# ECU_Sheet1.net
KiCad netlist of a schematic drawn in Altium Designer
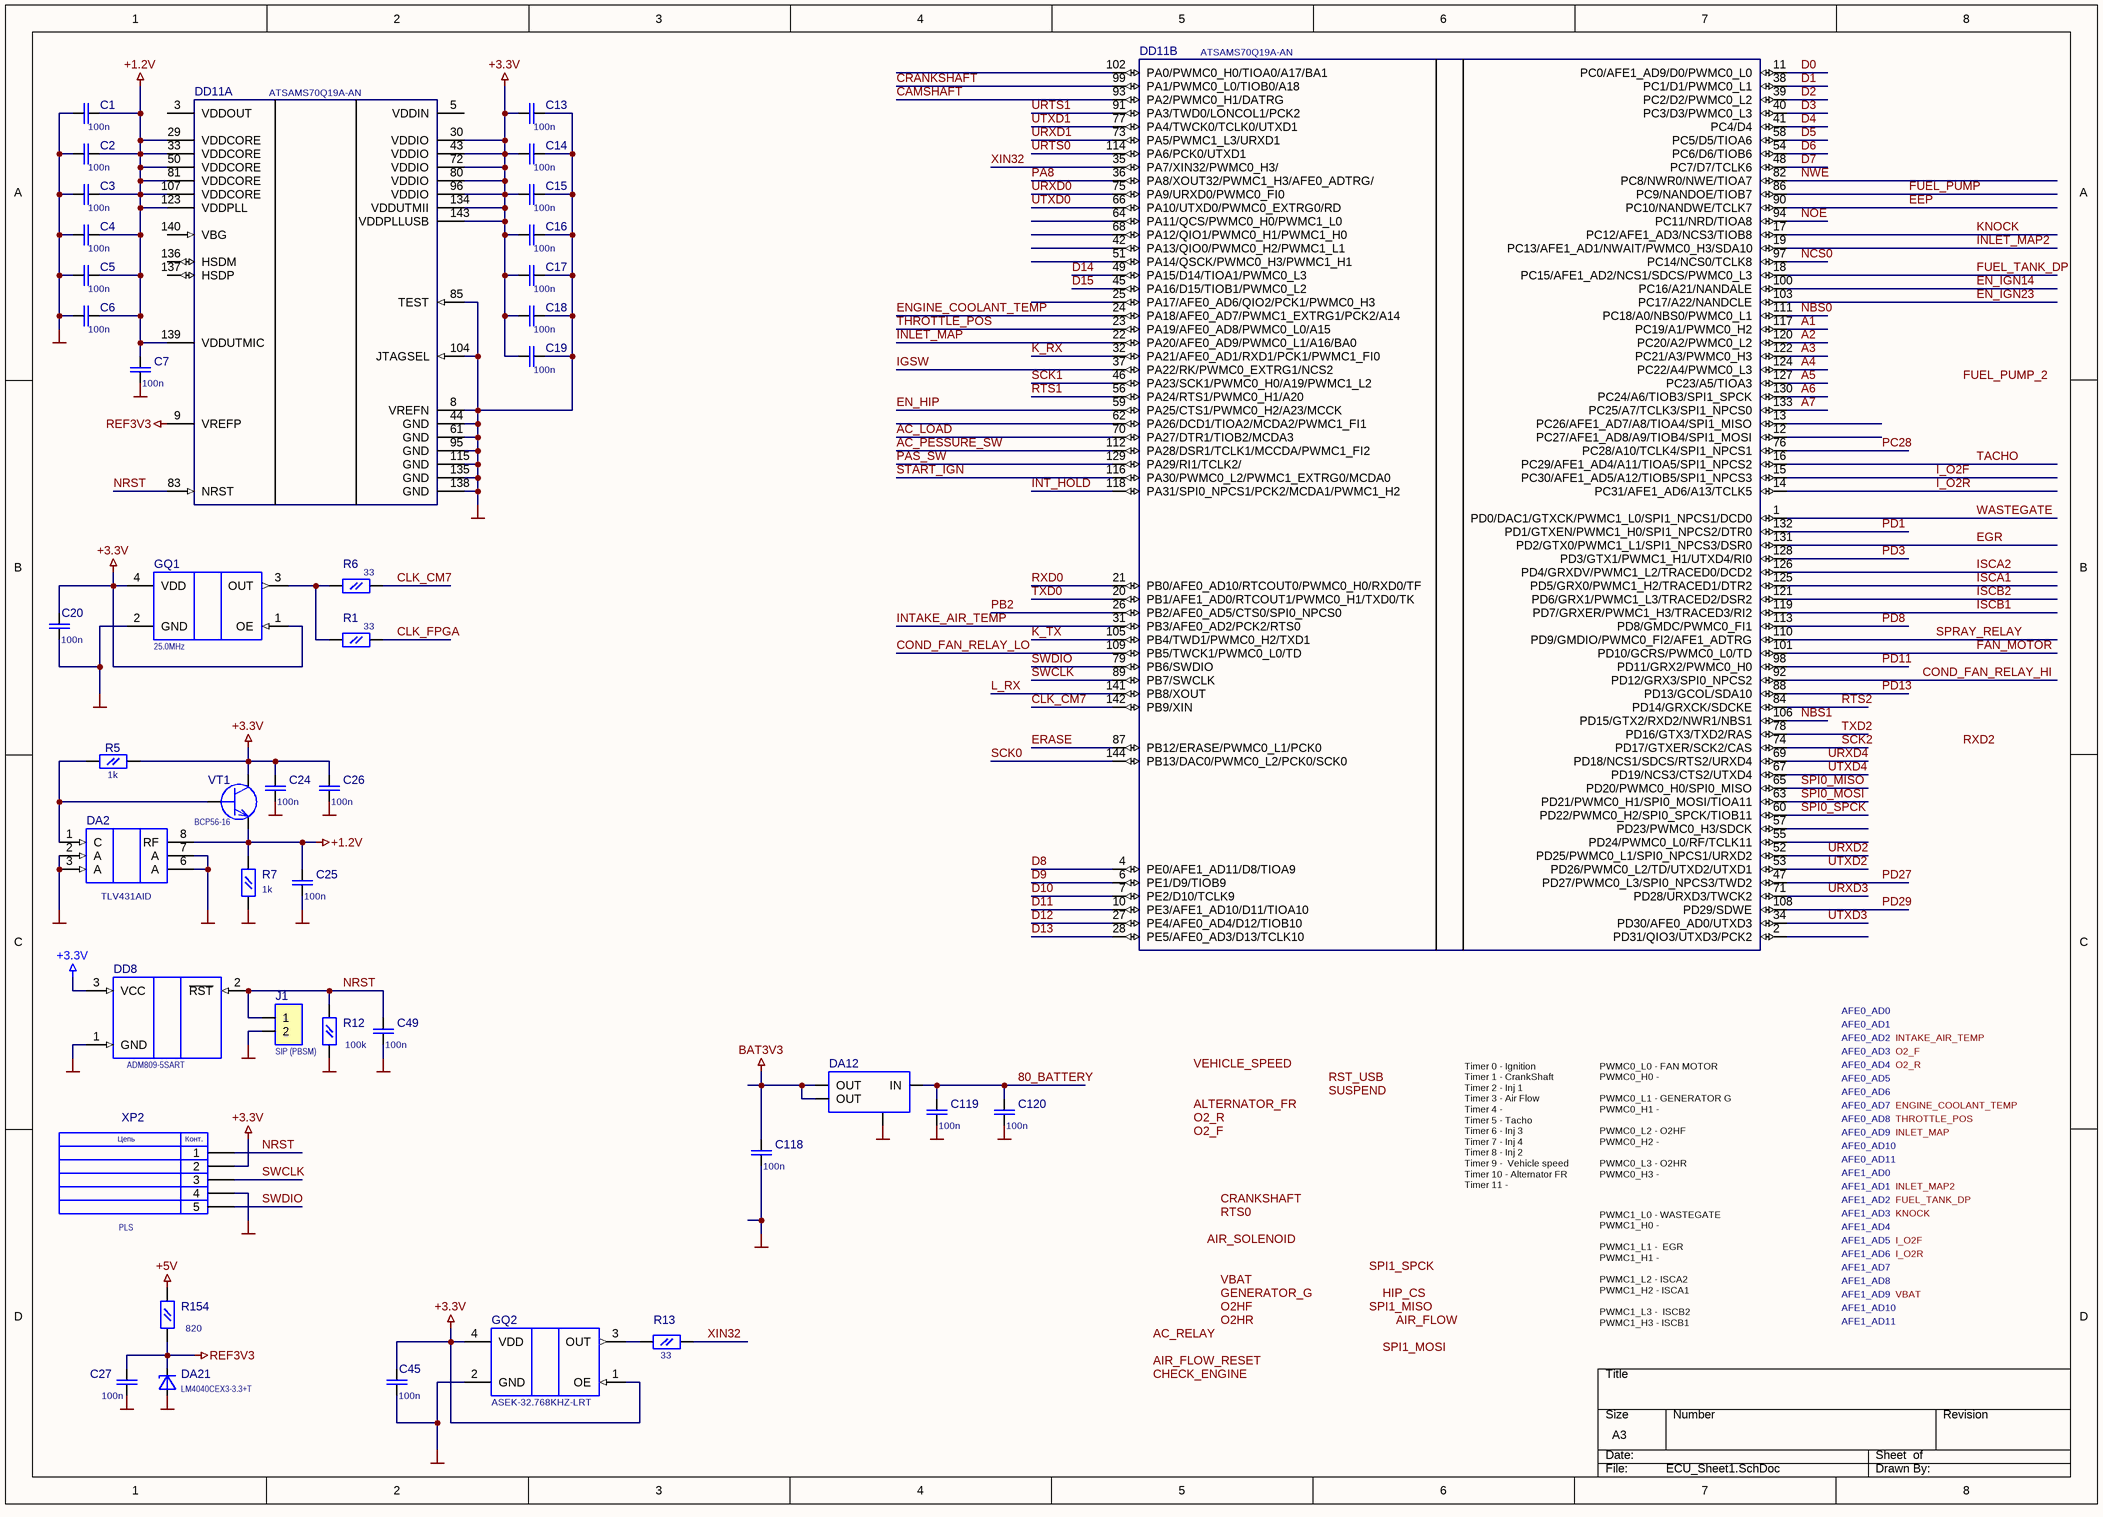
[diagram p0: ECU_Sheet1.SchDoc]

(export (version "E")
  (design (tool "Eeschema 10.0.6"))
  (components
    (comp (ref "C1")
      (value "100n")
      (footprint "C0603L")
      (description "C0603")
      (fields (field (name "Comment") "0.1мкФ-25В-X8R-10%"))
      (libsource (lib "L1") (part "CSMD"))
    )
    (comp (ref "C2")
      (value "100n")
      (footprint "C0603L")
      (description "C0603")
      (fields (field (name "Comment") "0.1мкФ-25В-X8R-10%"))
      (libsource (lib "L1") (part "CSMD"))
    )
    (comp (ref "C3")
      (value "100n")
      (footprint "C0603L")
      (description "C0603")
      (fields (field (name "Comment") "0.1мкФ-25В-X8R-10%"))
      (libsource (lib "L1") (part "CSMD"))
    )
    (comp (ref "C4")
      (value "100n")
      (footprint "C0603L")
      (description "C0603")
      (fields (field (name "Comment") "0.1мкФ-25В-X8R-10%"))
      (libsource (lib "L1") (part "CSMD"))
    )
    (comp (ref "C5")
      (value "100n")
      (footprint "C0603L")
      (description "C0603")
      (fields (field (name "Comment") "0.1мкФ-25В-X8R-10%"))
      (libsource (lib "L1") (part "CSMD"))
    )
    (comp (ref "C6")
      (value "100n")
      (footprint "C0603L")
      (description "C0603")
      (fields (field (name "Comment") "0.1мкФ-25В-X8R-10%"))
      (libsource (lib "L1") (part "CSMD"))
    )
    (comp (ref "C7")
      (value "100n")
      (footprint "C0603L")
      (description "C0603")
      (fields (field (name "Comment") "0.1мкФ-25В-X8R-10%"))
      (libsource (lib "L1") (part "CSMD"))
    )
    (comp (ref "C13")
      (value "100n")
      (footprint "C0603L")
      (description "C0603")
      (fields (field (name "Comment") "0.1мкФ-25В-X8R-10%"))
      (libsource (lib "L1") (part "CSMD"))
    )
    (comp (ref "C14")
      (value "100n")
      (footprint "C0603L")
      (description "C0603")
      (fields (field (name "Comment") "0.1мкФ-25В-X8R-10%"))
      (libsource (lib "L1") (part "CSMD"))
    )
    (comp (ref "C15")
      (value "100n")
      (footprint "C0603L")
      (description "C0603")
      (fields (field (name "Comment") "0.1мкФ-25В-X8R-10%"))
      (libsource (lib "L1") (part "CSMD"))
    )
    (comp (ref "C16")
      (value "100n")
      (footprint "C0603L")
      (description "C0603")
      (fields (field (name "Comment") "0.1мкФ-25В-X8R-10%"))
      (libsource (lib "L1") (part "CSMD"))
    )
    (comp (ref "C17")
      (value "100n")
      (footprint "C0603L")
      (description "C0603")
      (fields (field (name "Comment") "0.1мкФ-25В-X8R-10%"))
      (libsource (lib "L1") (part "CSMD"))
    )
    (comp (ref "C18")
      (value "100n")
      (footprint "C0603L")
      (description "C0603")
      (fields (field (name "Comment") "0.1мкФ-25В-X8R-10%"))
      (libsource (lib "L1") (part "CSMD"))
    )
    (comp (ref "C19")
      (value "100n")
      (footprint "C0603L")
      (description "C0603")
      (fields (field (name "Comment") "0.1мкФ-25В-X8R-10%"))
      (libsource (lib "L1") (part "CSMD"))
    )
    (comp (ref "C20")
      (value "100n")
      (footprint "C0805L")
      (description "C0603")
      (fields (field (name "Comment") "0.01мкФ-50В-X8R-10%"))
      (libsource (lib "L1") (part "CSMD"))
    )
    (comp (ref "C24")
      (value "100n")
      (footprint "C0805L")
      (description "C0603")
      (fields (field (name "Comment") "0.1мкФ-25В-X8R-10%"))
      (libsource (lib "L1") (part "CSMD"))
    )
    (comp (ref "C25")
      (value "100n")
      (footprint "C0805L")
      (description "C0603")
      (fields (field (name "Comment") "0.1мкФ-25В-X8R-10%"))
      (libsource (lib "L1") (part "CSMD"))
    )
    (comp (ref "C26")
      (value "100n")
      (footprint "C0805L")
      (description "C0603")
      (fields (field (name "Comment") "0.1мкФ-25В-X8R-10%"))
      (libsource (lib "L1") (part "CSMD"))
    )
    (comp (ref "C27")
      (value "100n")
      (footprint "C0603L")
      (description "C0603")
      (fields (field (name "Comment") "0.1мкФ-25В-X8R-10%"))
      (libsource (lib "L1") (part "CSMD"))
    )
    (comp (ref "C45")
      (value "100n")
      (footprint "C0805L")
      (description "C0603")
      (fields (field (name "Comment") "0.01мкФ-50В-X8R-10%"))
      (libsource (lib "L1") (part "CSMD"))
    )
    (comp (ref "C49")
      (value "100n")
      (footprint "C0603L")
      (description "C0603")
      (fields (field (name "Comment") "0.1мкФ-25В-X8R-10%"))
      (libsource (lib "L1") (part "CSMD"))
    )
    (comp (ref "C118")
      (value "100n")
      (footprint "C0805L")
      (description "C0603")
      (fields (field (name "Comment") "0.1мкФ-25В-X8R-10%"))
      (libsource (lib "L1") (part "CSMD"))
    )
    (comp (ref "C119")
      (value "100n")
      (footprint "C0805L")
      (description "C0603")
      (fields (field (name "Comment") "CSMD"))
      (libsource (lib "L1") (part "CSMD"))
    )
    (comp (ref "C120")
      (value "100n")
      (footprint "C0805L")
      (description "C0603")
      (fields (field (name "Comment") "CSMD"))
      (libsource (lib "L1") (part "CSMD"))
    )
    (comp (ref "DA2") (value "TLV431AID") (footprint "SOIC8 JEDEC") (libsource (lib "L1") (part "TL431AID")))
    (comp (ref "DA12")
      (value "LM1117IMP-3.3")
      (footprint "SOT-223")
      (libsource (lib "RL1") (part "LM1117IMP-3.3"))
    )
    (comp (ref "DA21")
      (value "LM4040CEX3-3.3+T")
      (footprint "RL1:SOT-23")
      (description "Improved Precision Micropower Shunt Voltage Reference")
      (libsource (lib "L1") (part "LM4040"))
    )
    (comp (ref "DD8")
      (value "ADM809-5SART")
      (footprint "RL1:SOT-23")
      (libsource (lib "L1") (part "ADM809-5SART"))
    )
    (comp (ref "DD11")
      (value "ATSAMS70Q19A-AN")
      (footprint "LQFP144")
      (libsource (lib "L1") (part "ATSAMS70Q19A-AN"))
    )
    (comp (ref "GQ1")
      (value "25.0MHz")
      (footprint "KXO-97")
      (description "KXO-V97T 25.0 MHz")
      (libsource (lib "L1") (part "KXO-V97T"))
    )
    (comp (ref "GQ2")
      (value "ASEK-32.768KHZ-LRT")
      (footprint "QUARTZ-3.2mm-2.5mm")
      (libsource (lib "RL1") (part "ASEMB-50.000MHZ-LY"))
    )
    (comp (ref "J1") (value "SIP (PBSM)") (footprint "SIP1X2S") (libsource (lib "SCH") (part "CON2")))
    (comp (ref "R1")
      (value "33")
      (footprint "R0603L")
      (description "R0805")
      (fields (field (name "Comment") "33-5%"))
      (libsource (lib "L1") (part "RSMD"))
    )
    (comp (ref "R5")
      (value "1k")
      (footprint "R0805")
      (description "R0805")
      (fields (field (name "Comment") "1к-5%"))
      (libsource (lib "L1") (part "RSMD"))
    )
    (comp (ref "R6")
      (value "33")
      (footprint "R0603L")
      (description "R0805")
      (fields (field (name "Comment") "33-5%"))
      (libsource (lib "L1") (part "RSMD"))
    )
    (comp (ref "R7")
      (value "1k")
      (footprint "R0805L")
      (description "R0805")
      (fields (field (name "Comment") "1к-5%"))
      (libsource (lib "L1") (part "RSMD"))
    )
    (comp (ref "R12")
      (value "100k")
      (footprint "R0805L")
      (description "R0805")
      (fields (field (name "Comment") "100к-5%"))
      (libsource (lib "L1") (part "RSMD"))
    )
    (comp (ref "R13")
      (value "33")
      (footprint "R0603L")
      (description "R0805")
      (fields (field (name "Comment") "33-5%"))
      (libsource (lib "L1") (part "RSMD"))
    )
    (comp (ref "R154")
      (value "820")
      (footprint "R0805L")
      (description "R0805")
      (fields (field (name "Comment") "100к-5%"))
      (libsource (lib "L1") (part "RSMD"))
    )
    (comp (ref "VT1") (value "BCP56-16") (footprint "SOT-223 PWR") (libsource (lib "L1") (part "BCP56-16")))
    (comp (ref "XP2")
      (value "PLS")
      (footprint "SIP5")
      (description "CONNSIP5")
      (libsource (lib "RL1") (part "CONNSIP5"))
    )
  )
  (nets
    (net (code "1") (name "+1.2V") (class "Default")
      (node (ref "C1") (pin "1") (pintype "passive"))
      (node (ref "C2") (pin "1") (pintype "passive"))
      (node (ref "C25") (pin "1") (pintype "passive"))
      (node (ref "C3") (pin "1") (pintype "passive"))
      (node (ref "C4") (pin "1") (pintype "passive"))
      (node (ref "C5") (pin "1") (pintype "passive"))
      (node (ref "C6") (pin "1") (pintype "passive"))
      (node (ref "C7") (pin "1") (pintype "passive"))
      (node (ref "DA2") (pin "8") (pinfunction "RF_8") (pintype "power_in"))
      (node (ref "DD11") (pin "107") (pinfunction "VDDCORE_107") (pintype "power_in"))
      (node (ref "DD11") (pin "123") (pinfunction "VDDPLL_123") (pintype "power_in"))
      (node (ref "DD11") (pin "139") (pinfunction "VDDUTMIC_139") (pintype "power_in"))
      (node (ref "DD11") (pin "29") (pinfunction "VDDCORE_29") (pintype "power_in"))
      (node (ref "DD11") (pin "33") (pinfunction "VDDCORE_33") (pintype "power_in"))
      (node (ref "DD11") (pin "50") (pinfunction "VDDCORE_50") (pintype "power_in"))
      (node (ref "DD11") (pin "81") (pinfunction "VDDCORE_81") (pintype "power_in"))
      (node (ref "R7") (pin "2") (pinfunction "Pin2_2") (pintype "passive"))
      (node (ref "VT1") (pin "3") (pinfunction "E_3") (pintype "passive"))
    )
    (net (code "2") (name "+3.3V") (class "Default")
      (node (ref "C13") (pin "2") (pintype "passive"))
      (node (ref "C14") (pin "2") (pintype "passive"))
      (node (ref "C15") (pin "2") (pintype "passive"))
      (node (ref "C16") (pin "2") (pintype "passive"))
      (node (ref "C17") (pin "2") (pintype "passive"))
      (node (ref "C18") (pin "2") (pintype "passive"))
      (node (ref "C19") (pin "2") (pintype "passive"))
      (node (ref "C20") (pin "2") (pintype "passive"))
      (node (ref "C24") (pin "1") (pintype "passive"))
      (node (ref "C26") (pin "1") (pintype "passive"))
      (node (ref "C45") (pin "2") (pintype "passive"))
      (node (ref "DD11") (pin "134") (pinfunction "VDDUTMII_134") (pintype "power_in"))
      (node (ref "DD11") (pin "143") (pinfunction "VDDPLLUSB_143") (pintype "power_in"))
      (node (ref "DD11") (pin "30") (pinfunction "VDDIO_30") (pintype "power_in"))
      (node (ref "DD11") (pin "43") (pinfunction "VDDIO_43") (pintype "power_in"))
      (node (ref "DD11") (pin "72") (pinfunction "VDDIO_72") (pintype "power_in"))
      (node (ref "DD11") (pin "80") (pinfunction "VDDIO_80") (pintype "power_in"))
      (node (ref "DD11") (pin "96") (pinfunction "VDDIO_96") (pintype "power_in"))
      (node (ref "DD8") (pin "3") (pinfunction "VCC_3") (pintype "input"))
      (node (ref "GQ1") (pin "1") (pinfunction "OE_1") (pintype "input"))
      (node (ref "GQ1") (pin "4") (pinfunction "VDD_4") (pintype "power_in"))
      (node (ref "GQ2") (pin "1") (pinfunction "OE_1") (pintype "input"))
      (node (ref "GQ2") (pin "4") (pinfunction "VDD_4") (pintype "power_in"))
      (node (ref "R5") (pin "1") (pinfunction "Pin1_1") (pintype "passive"))
      (node (ref "VT1") (pin "2") (pinfunction "C_2") (pintype "passive"))
      (node (ref "XP2") (pin "2") (pinfunction "2_2") (pintype "passive"))
    )
    (net (code "3") (name "+5V") (class "Default")
      (node (ref "R154") (pin "2") (pinfunction "Pin2_2") (pintype "passive"))
    )
    (net (code "4") (name "/80_BATTERY") (class "Default")
      (node (ref "C119") (pin "1") (pintype "passive"))
      (node (ref "C120") (pin "1") (pintype "passive"))
      (node (ref "DA12") (pin "3") (pinfunction "IN_3") (pintype "passive"))
    )
    (net (code "5") (name "/A1") (class "Default")
      (node (ref "DD11") (pin "117") (pinfunction "PC19/A1/PWMC0_H2_117") (pintype "bidirectional"))
    )
    (net (code "6") (name "/A2") (class "Default")
      (node (ref "DD11") (pin "120") (pinfunction "PC20/A2/PWMC0_L2_120") (pintype "bidirectional"))
    )
    (net (code "7") (name "/A3") (class "Default")
      (node (ref "DD11") (pin "122") (pinfunction "PC21/A3/PWMC0_H3_122") (pintype "bidirectional"))
    )
    (net (code "8") (name "/A4") (class "Default")
      (node (ref "DD11") (pin "124") (pinfunction "PC22/A4/PWMC0_L3_124") (pintype "bidirectional"))
    )
    (net (code "9") (name "/A5") (class "Default")
      (node (ref "DD11") (pin "127") (pinfunction "PC23/A5/TIOA3_127") (pintype "bidirectional"))
    )
    (net (code "10") (name "/A6") (class "Default")
      (node (ref "DD11") (pin "130") (pinfunction "PC24/A6/TIOB3/SPI1_SPCK_130") (pintype "bidirectional"))
    )
    (net (code "11") (name "/A7") (class "Default")
      (node (ref "DD11") (pin "133") (pinfunction "PC25/A7/TCLK3/SPI1_NPCS0_133") (pintype "bidirectional"))
    )
    (net (code "12") (name "/AC_LOAD") (class "Default")
      (node (ref "DD11") (pin "70") (pinfunction "PA27/DTR1/TIOB2/MCDA3_70") (pintype "bidirectional"))
    )
    (net (code "13") (name "/AC_PESSURE_SW") (class "Default")
      (node (ref "DD11") (pin "112") (pinfunction "PA28/DSR1/TCLK1/MCCDA/PWMC1_FI2_112") (pintype "bidirectional"))
    )
    (net (code "19") (name "/CAMSHAFT") (class "Default")
      (node (ref "DD11") (pin "93") (pinfunction "PA2/PWMC0_H1/DATRG_93") (pintype "bidirectional"))
    )
    (net (code "21") (name "/CLK_CM7") (class "Default")
      (node (ref "DD11") (pin "142") (pinfunction "PB9/XIN_142") (pintype "bidirectional"))
      (node (ref "R6") (pin "2") (pinfunction "Pin2_2") (pintype "passive"))
    )
    (net (code "22") (name "/CLK_FPGA") (class "Default")
      (node (ref "R1") (pin "2") (pinfunction "Pin2_2") (pintype "passive"))
    )
    (net (code "23") (name "/COND_FAN_RELAY_HI") (class "Default")
      (node (ref "DD11") (pin "92") (pinfunction "PD12/GRX3/SPI0_NPCS2_92") (pintype "bidirectional"))
    )
    (net (code "24") (name "/COND_FAN_RELAY_LO") (class "Default")
      (node (ref "DD11") (pin "109") (pinfunction "PB5/TWCK1/PWMC0_L0/TD_109") (pintype "bidirectional"))
    )
    (net (code "25") (name "/CRANKSHAFT") (class "Default")
      (node (ref "DD11") (pin "99") (pinfunction "PA1/PWMC0_L0/TIOB0/A18_99") (pintype "bidirectional"))
    )
    (net (code "26") (name "/D0") (class "Default")
      (node (ref "DD11") (pin "11") (pinfunction "PC0/AFE1_AD9/D0/PWMC0_L0_11") (pintype "bidirectional"))
    )
    (net (code "27") (name "/D1") (class "Default")
      (node (ref "DD11") (pin "38") (pinfunction "PC1/D1/PWMC0_L1_38") (pintype "bidirectional"))
    )
    (net (code "28") (name "/D2") (class "Default")
      (node (ref "DD11") (pin "39") (pinfunction "PC2/D2/PWMC0_L2_39") (pintype "bidirectional"))
    )
    (net (code "29") (name "/D3") (class "Default")
      (node (ref "DD11") (pin "40") (pinfunction "PC3/D3/PWMC0_L3_40") (pintype "bidirectional"))
    )
    (net (code "30") (name "/D4") (class "Default")
      (node (ref "DD11") (pin "41") (pinfunction "PC4/D4_41") (pintype "bidirectional"))
    )
    (net (code "31") (name "/D5") (class "Default")
      (node (ref "DD11") (pin "58") (pinfunction "PC5/D5/TIOA6_58") (pintype "bidirectional"))
    )
    (net (code "32") (name "/D6") (class "Default")
      (node (ref "DD11") (pin "54") (pinfunction "PC6/D6/TIOB6_54") (pintype "bidirectional"))
    )
    (net (code "33") (name "/D7") (class "Default")
      (node (ref "DD11") (pin "48") (pinfunction "PC7/D7/TCLK6_48") (pintype "bidirectional"))
    )
    (net (code "34") (name "/D8") (class "Default")
      (node (ref "DD11") (pin "4") (pinfunction "PE0/AFE1_AD11/D8/TIOA9_4") (pintype "bidirectional"))
    )
    (net (code "35") (name "/D9") (class "Default")
      (node (ref "DD11") (pin "6") (pinfunction "PE1/D9/TIOB9_6") (pintype "bidirectional"))
    )
    (net (code "36") (name "/D10") (class "Default")
      (node (ref "DD11") (pin "7") (pinfunction "PE2/D10/TCLK9_7") (pintype "bidirectional"))
    )
    (net (code "37") (name "/D11") (class "Default")
      (node (ref "DD11") (pin "10") (pinfunction "PE3/AFE1_AD10/D11/TIOA10_10") (pintype "bidirectional"))
    )
    (net (code "38") (name "/D12") (class "Default")
      (node (ref "DD11") (pin "27") (pinfunction "PE4/AFE0_AD4/D12/TIOB10_27") (pintype "bidirectional"))
    )
    (net (code "39") (name "/D13") (class "Default")
      (node (ref "DD11") (pin "28") (pinfunction "PE5/AFE0_AD3/D13/TCLK10_28") (pintype "bidirectional"))
    )
    (net (code "40") (name "/D14") (class "Default")
      (node (ref "DD11") (pin "49") (pinfunction "PA15/D14/TIOA1/PWMC0_L3_49") (pintype "bidirectional"))
    )
    (net (code "41") (name "/D15") (class "Default")
      (node (ref "DD11") (pin "45") (pinfunction "PA16/D15/TIOB1/PWMC0_L2_45") (pintype "bidirectional"))
    )
    (net (code "42") (name "/EEP") (class "Default")
      (node (ref "DD11") (pin "90") (pinfunction "PC10/NANDWE/TCLK7_90") (pintype "bidirectional"))
    )
    (net (code "43") (name "/EGR") (class "Default")
      (node (ref "DD11") (pin "131") (pinfunction "PD2/GTX0/PWMC1_L1/SPI1_NPCS3/DSR0_131") (pintype "bidirectional"))
    )
    (net (code "44") (name "/ENGINE_COOLANT_TEMP") (class "Default")
      (node (ref "DD11") (pin "24") (pinfunction "PA18/AFE0_AD7/PWMC1_EXTRG1/PCK2/A14_24") (pintype "bidirectional"))
    )
    (net (code "45") (name "/EN_HIP") (class "Default")
      (node (ref "DD11") (pin "59") (pinfunction "PA25/CTS1/PWMC0_H2/A23/MCCK_59") (pintype "bidirectional"))
    )
    (net (code "46") (name "/EN_IGN14") (class "Default")
      (node (ref "DD11") (pin "100") (pinfunction "PC16/A21/NANDALE_100") (pintype "bidirectional"))
    )
    (net (code "47") (name "/EN_IGN23") (class "Default")
      (node (ref "DD11") (pin "103") (pinfunction "PC17/A22/NANDCLE_103") (pintype "bidirectional"))
    )
    (net (code "48") (name "/ERASE") (class "Default")
      (node (ref "DD11") (pin "87") (pinfunction "PB12/ERASE/PWMC0_L1/PCK0_87") (pintype "bidirectional"))
    )
    (net (code "49") (name "/FAN_MOTOR") (class "Default")
      (node (ref "DD11") (pin "101") (pinfunction "PD10/GCRS/PWMC0_L0/TD_101") (pintype "bidirectional"))
    )
    (net (code "50") (name "/FUEL_PUMP") (class "Default")
      (node (ref "DD11") (pin "86") (pinfunction "PC9/NANDOE/TIOB7_86") (pintype "bidirectional"))
    )
    (net (code "52") (name "/FUEL_TANK_DP") (class "Default")
      (node (ref "DD11") (pin "18") (pinfunction "PC15/AFE1_AD2/NCS1/SDCS/PWMC0_L3_18") (pintype "bidirectional"))
    )
    (net (code "55") (name "/IGSW") (class "Default")
      (node (ref "DD11") (pin "37") (pinfunction "PA22/RK/PWMC0_EXTRG1/NCS2_37") (pintype "bidirectional"))
    )
    (net (code "56") (name "/INLET_MAP") (class "Default")
      (node (ref "DD11") (pin "22") (pinfunction "PA20/AFE0_AD9/PWMC0_L1/A16/BA0_22") (pintype "bidirectional"))
    )
    (net (code "57") (name "/INLET_MAP2") (class "Default")
      (node (ref "DD11") (pin "19") (pinfunction "PC13/AFE1_AD1/NWAIT/PWMC0_H3/SDA10_19") (pintype "bidirectional"))
    )
    (net (code "58") (name "/INTAKE_AIR_TEMP") (class "Default")
      (node (ref "DD11") (pin "31") (pinfunction "PB3/AFE0_AD2/PCK2/RTS0_31") (pintype "bidirectional"))
    )
    (net (code "59") (name "/INT_HOLD") (class "Default")
      (node (ref "DD11") (pin "118") (pinfunction "PA31/SPI0_NPCS1/PCK2/MCDA1/PWMC1_H2_118") (pintype "bidirectional"))
    )
    (net (code "60") (name "/ISCA1") (class "Default")
      (node (ref "DD11") (pin "125") (pinfunction "PD5/GRX0/PWMC1_H2/TRACED1/DTR2_125") (pintype "bidirectional"))
    )
    (net (code "61") (name "/ISCA2") (class "Default")
      (node (ref "DD11") (pin "126") (pinfunction "PD4/GRXDV/PWMC1_L2/TRACED0/DCD2_126") (pintype "bidirectional"))
    )
    (net (code "62") (name "/ISCB1") (class "Default")
      (node (ref "DD11") (pin "119") (pinfunction "PD7/GRXER/PWMC1_H3/TRACED3/RI2_119") (pintype "bidirectional"))
    )
    (net (code "63") (name "/ISCB2") (class "Default")
      (node (ref "DD11") (pin "121") (pinfunction "PD6/GRX1/PWMC1_L3/TRACED2/DSR2_121") (pintype "bidirectional"))
    )
    (net (code "64") (name "/I_O2F") (class "Default")
      (node (ref "DD11") (pin "15") (pinfunction "PC30/AFE1_AD5/A12/TIOB5/SPI1_NPCS3_15") (pintype "bidirectional"))
    )
    (net (code "65") (name "/I_O2R") (class "Default")
      (node (ref "DD11") (pin "14") (pinfunction "PC31/AFE1_AD6/A13/TCLK5_14") (pintype "bidirectional"))
    )
    (net (code "66") (name "/KNOCK") (class "Default")
      (node (ref "DD11") (pin "17") (pinfunction "PC12/AFE1_AD3/NCS3/TIOB8_17") (pintype "bidirectional"))
    )
    (net (code "67") (name "/K_RX") (class "Default")
      (node (ref "DD11") (pin "32") (pinfunction "PA21/AFE0_AD1/RXD1/PCK1/PWMC1_FI0_32") (pintype "bidirectional"))
    )
    (net (code "68") (name "/K_TX") (class "Default")
      (node (ref "DD11") (pin "105") (pinfunction "PB4/TWD1/PWMC0_H2/TXD1_105") (pintype "bidirectional"))
    )
    (net (code "69") (name "/L_RX") (class "Default")
      (node (ref "DD11") (pin "141") (pinfunction "PB8/XOUT_141") (pintype "bidirectional"))
    )
    (net (code "70") (name "/NBS0") (class "Default")
      (node (ref "DD11") (pin "111") (pinfunction "PC18/A0/NBS0/PWMC0_L1_111") (pintype "bidirectional"))
    )
    (net (code "71") (name "/NBS1") (class "Default")
      (node (ref "DD11") (pin "106") (pinfunction "PD15/GTX2/RXD2/NWR1/NBS1_106") (pintype "bidirectional"))
    )
    (net (code "72") (name "/NCS0") (class "Default")
      (node (ref "DD11") (pin "97") (pinfunction "PC14/NCS0/TCLK8_97") (pintype "bidirectional"))
    )
    (net (code "73") (name "/NOE") (class "Default")
      (node (ref "DD11") (pin "94") (pinfunction "PC11/NRD/TIOA8_94") (pintype "bidirectional"))
    )
    (net (code "74") (name "/NRST") (class "Default")
      (node (ref "C49") (pin "1") (pintype "passive"))
      (node (ref "DD11") (pin "83") (pinfunction "NRST_83") (pintype "input"))
      (node (ref "DD8") (pin "2") (pinfunction "~{RST}_2") (pintype "input"))
      (node (ref "J1") (pin "1") (pinfunction "1_1") (pintype "passive"))
      (node (ref "R12") (pin "2") (pinfunction "Pin2_2") (pintype "passive"))
      (node (ref "XP2") (pin "1") (pinfunction "1_1") (pintype "passive"))
    )
    (net (code "75") (name "/NWE") (class "Default")
      (node (ref "DD11") (pin "82") (pinfunction "PC8/NWR0/NWE/TIOA7_82") (pintype "bidirectional"))
    )
    (net (code "80") (name "/PA8") (class "Default")
      (node (ref "DD11") (pin "36") (pinfunction "PA8/XOUT32/PWMC1_H3/AFE0_ADTRG/_36") (pintype "bidirectional"))
    )
    (net (code "81") (name "/PAS_SW") (class "Default")
      (node (ref "DD11") (pin "129") (pinfunction "PA29/RI1/TCLK2/_129") (pintype "bidirectional"))
    )
    (net (code "82") (name "/PB2") (class "Default")
      (node (ref "DD11") (pin "26") (pinfunction "PB2/AFE0_AD5/CTS0/SPI0_NPCS0_26") (pintype "bidirectional"))
    )
    (net (code "83") (name "/PC28") (class "Default")
      (node (ref "DD11") (pin "76") (pinfunction "PC28/A10/TCLK4/SPI1_NPCS1_76") (pintype "bidirectional"))
    )
    (net (code "84") (name "/PD1") (class "Default")
      (node (ref "DD11") (pin "132") (pinfunction "PD1/GTXEN/PWMC1_H0/SPI1_NPCS2/DTR0_132") (pintype "bidirectional"))
    )
    (net (code "85") (name "/PD3") (class "Default")
      (node (ref "DD11") (pin "128") (pinfunction "PD3/GTX1/PWMC1_H1/UTXD4/RI0_128") (pintype "bidirectional"))
    )
    (net (code "86") (name "/PD8") (class "Default")
      (node (ref "DD11") (pin "113") (pinfunction "PD8/GMDC/PWMC0_FI1_113") (pintype "bidirectional"))
    )
    (net (code "87") (name "/PD11") (class "Default")
      (node (ref "DD11") (pin "98") (pinfunction "PD11/GRX2/PWMC0_H0_98") (pintype "bidirectional"))
    )
    (net (code "88") (name "/PD13") (class "Default")
      (node (ref "DD11") (pin "88") (pinfunction "PD13/GCOL/SDA10_88") (pintype "bidirectional"))
    )
    (net (code "89") (name "/PD27") (class "Default")
      (node (ref "DD11") (pin "47") (pinfunction "PD27/PWMC0_L3/SPI0_NPCS3/TWD2_47") (pintype "bidirectional"))
    )
    (net (code "90") (name "/PD29") (class "Default")
      (node (ref "DD11") (pin "108") (pinfunction "PD29/SDWE_108") (pintype "bidirectional"))
    )
    (net (code "93") (name "/RTS1") (class "Default")
      (node (ref "DD11") (pin "56") (pinfunction "PA24/RTS1/PWMC0_H1/A20_56") (pintype "bidirectional"))
    )
    (net (code "94") (name "/RTS2") (class "Default")
      (node (ref "DD11") (pin "84") (pinfunction "PD14/GRXCK/SDCKE_84") (pintype "bidirectional"))
    )
    (net (code "95") (name "/RXD0") (class "Default")
      (node (ref "DD11") (pin "21") (pinfunction "PB0/AFE0_AD10/RTCOUT0/PWMC0_H0/RXD0/TF_21") (pintype "bidirectional"))
    )
    (net (code "97") (name "/SCK0") (class "Default")
      (node (ref "DD11") (pin "144") (pinfunction "PB13/DAC0/PWMC0_L2/PCK0/SCK0_144") (pintype "bidirectional"))
    )
    (net (code "98") (name "/SCK1") (class "Default")
      (node (ref "DD11") (pin "46") (pinfunction "PA23/SCK1/PWMC0_H0/A19/PWMC1_L2_46") (pintype "bidirectional"))
    )
    (net (code "99") (name "/SCK2") (class "Default")
      (node (ref "DD11") (pin "74") (pinfunction "PD17/GTXER/SCK2/CAS_74") (pintype "bidirectional"))
    )
    (net (code "100") (name "/SPI0_MISO") (class "Default")
      (node (ref "DD11") (pin "65") (pinfunction "PD20/PWMC0_H0/SPI0_MISO_65") (pintype "bidirectional"))
    )
    (net (code "101") (name "/SPI0_MOSI") (class "Default")
      (node (ref "DD11") (pin "63") (pinfunction "PD21/PWMC0_H1/SPI0_MOSI/TIOA11_63") (pintype "bidirectional"))
    )
    (net (code "102") (name "/SPI0_SPCK") (class "Default")
      (node (ref "DD11") (pin "60") (pinfunction "PD22/PWMC0_H2/SPI0_SPCK/TIOB11_60") (pintype "bidirectional"))
    )
    (net (code "106") (name "/SPRAY_RELAY") (class "Default")
      (node (ref "DD11") (pin "110") (pinfunction "PD9/GMDIO/PWMC0_FI2/AFE1_ADTRG_110") (pintype "bidirectional"))
    )
    (net (code "107") (name "/START_IGN") (class "Default")
      (node (ref "DD11") (pin "116") (pinfunction "PA30/PWMC0_L2/PWMC1_EXTRG0/MCDA0_116") (pintype "bidirectional"))
    )
    (net (code "109") (name "/SWCLK") (class "Default")
      (node (ref "DD11") (pin "89") (pinfunction "PB7/SWCLK_89") (pintype "bidirectional"))
      (node (ref "XP2") (pin "3") (pinfunction "3_3") (pintype "passive"))
    )
    (net (code "110") (name "/SWDIO") (class "Default")
      (node (ref "DD11") (pin "79") (pinfunction "PB6/SWDIO_79") (pintype "bidirectional"))
      (node (ref "XP2") (pin "5") (pinfunction "5_5") (pintype "passive"))
    )
    (net (code "111") (name "/TACHO") (class "Default")
      (node (ref "DD11") (pin "16") (pinfunction "PC29/AFE1_AD4/A11/TIOA5/SPI1_NPCS2_16") (pintype "bidirectional"))
    )
    (net (code "112") (name "/THROTTLE_POS") (class "Default")
      (node (ref "DD11") (pin "23") (pinfunction "PA19/AFE0_AD8/PWMC0_L0/A15_23") (pintype "bidirectional"))
    )
    (net (code "113") (name "/TXD0") (class "Default")
      (node (ref "DD11") (pin "20") (pinfunction "PB1/AFE1_AD0/RTCOUT1/PWMC0_H1/TXD0/TK_20") (pintype "bidirectional"))
    )
    (net (code "114") (name "/TXD2") (class "Default")
      (node (ref "DD11") (pin "78") (pinfunction "PD16/GTX3/TXD2/RAS_78") (pintype "bidirectional"))
    )
    (net (code "115") (name "/URTS0") (class "Default")
      (node (ref "DD11") (pin "114") (pinfunction "PA6/PCK0/UTXD1_114") (pintype "bidirectional"))
    )
    (net (code "116") (name "/URTS1") (class "Default")
      (node (ref "DD11") (pin "91") (pinfunction "PA3/TWD0/LONCOL1/PCK2_91") (pintype "bidirectional"))
    )
    (net (code "117") (name "/URXD0") (class "Default")
      (node (ref "DD11") (pin "75") (pinfunction "PA9/URXD0/PWMC0_FI0_75") (pintype "bidirectional"))
    )
    (net (code "118") (name "/URXD1") (class "Default")
      (node (ref "DD11") (pin "73") (pinfunction "PA5/PWMC1_L3/URXD1_73") (pintype "bidirectional"))
    )
    (net (code "119") (name "/URXD2") (class "Default")
      (node (ref "DD11") (pin "52") (pinfunction "PD25/PWMC0_L1/SPI0_NPCS1/URXD2_52") (pintype "bidirectional"))
    )
    (net (code "120") (name "/URXD3") (class "Default")
      (node (ref "DD11") (pin "71") (pinfunction "PD28/URXD3/TWCK2_71") (pintype "bidirectional"))
    )
    (net (code "121") (name "/URXD4") (class "Default")
      (node (ref "DD11") (pin "69") (pinfunction "PD18/NCS1/SDCS/RTS2/URXD4_69") (pintype "bidirectional"))
    )
    (net (code "122") (name "/UTXD0") (class "Default")
      (node (ref "DD11") (pin "66") (pinfunction "PA10/UTXD0/PWMC0_EXTRG0/RD_66") (pintype "bidirectional"))
    )
    (net (code "123") (name "/UTXD1") (class "Default")
      (node (ref "DD11") (pin "77") (pinfunction "PA4/TWCK0/TCLK0/UTXD1_77") (pintype "bidirectional"))
    )
    (net (code "124") (name "/UTXD2") (class "Default")
      (node (ref "DD11") (pin "53") (pinfunction "PD26/PWMC0_L2/TD/UTXD2/UTXD1_53") (pintype "bidirectional"))
    )
    (net (code "125") (name "/UTXD3") (class "Default")
      (node (ref "DD11") (pin "34") (pinfunction "PD30/AFE0_AD0/UTXD3_34") (pintype "bidirectional"))
    )
    (net (code "126") (name "/UTXD4") (class "Default")
      (node (ref "DD11") (pin "67") (pinfunction "PD19/NCS3/CTS2/UTXD4_67") (pintype "bidirectional"))
    )
    (net (code "129") (name "/WASTEGATE") (class "Default")
      (node (ref "DD11") (pin "1") (pinfunction "PD0/DAC1/GTXCK/PWMC1_L0/SPI1_NPCS1/DCD0_1") (pintype "bidirectional"))
    )
    (net (code "130") (name "/XIN32") (class "Default")
      (node (ref "DD11") (pin "35") (pinfunction "PA7/XIN32/PWMC0_H3/_35") (pintype "bidirectional"))
      (node (ref "R13") (pin "2") (pinfunction "Pin2_2") (pintype "passive"))
    )
    (net (code "131") (name "BAT3V3") (class "Default")
      (node (ref "C118") (pin "1") (pintype "passive"))
      (node (ref "DA12") (pin "2") (pinfunction "OUT_2") (pintype "passive"))
      (node (ref "DA12") (pin "4") (pinfunction "OUT_4") (pintype "passive"))
    )
    (net (code "132") (name "GND") (class "Default")
      (node (ref "C1") (pin "2") (pintype "passive"))
      (node (ref "C118") (pin "2") (pintype "passive"))
      (node (ref "C119") (pin "2") (pintype "passive"))
      (node (ref "C120") (pin "2") (pintype "passive"))
      (node (ref "C13") (pin "1") (pintype "passive"))
      (node (ref "C14") (pin "1") (pintype "passive"))
      (node (ref "C15") (pin "1") (pintype "passive"))
      (node (ref "C16") (pin "1") (pintype "passive"))
      (node (ref "C17") (pin "1") (pintype "passive"))
      (node (ref "C18") (pin "1") (pintype "passive"))
      (node (ref "C19") (pin "1") (pintype "passive"))
      (node (ref "C2") (pin "2") (pintype "passive"))
      (node (ref "C20") (pin "1") (pintype "passive"))
      (node (ref "C24") (pin "2") (pintype "passive"))
      (node (ref "C25") (pin "2") (pintype "passive"))
      (node (ref "C26") (pin "2") (pintype "passive"))
      (node (ref "C27") (pin "2") (pintype "passive"))
      (node (ref "C3") (pin "2") (pintype "passive"))
      (node (ref "C4") (pin "2") (pintype "passive"))
      (node (ref "C45") (pin "1") (pintype "passive"))
      (node (ref "C49") (pin "2") (pintype "passive"))
      (node (ref "C5") (pin "2") (pintype "passive"))
      (node (ref "C6") (pin "2") (pintype "passive"))
      (node (ref "C7") (pin "2") (pintype "passive"))
      (node (ref "DA12") (pin "1") (pinfunction "G_1") (pintype "passive"))
      (node (ref "DA2") (pin "2") (pinfunction "A_2") (pintype "input"))
      (node (ref "DA2") (pin "3") (pinfunction "A_3") (pintype "input"))
      (node (ref "DA2") (pin "6") (pinfunction "A_6") (pintype "power_in"))
      (node (ref "DA2") (pin "7") (pinfunction "A_7") (pintype "power_in"))
      (node (ref "DA21") (pin "2") (pintype "passive"))
      (node (ref "DD11") (pin "104") (pinfunction "JTAGSEL_104") (pintype "input"))
      (node (ref "DD11") (pin "115") (pinfunction "GND_115") (pintype "power_in"))
      (node (ref "DD11") (pin "135") (pinfunction "GND_135") (pintype "power_in"))
      (node (ref "DD11") (pin "138") (pinfunction "GND_138") (pintype "power_in"))
      (node (ref "DD11") (pin "44") (pinfunction "GND_44") (pintype "power_in"))
      (node (ref "DD11") (pin "61") (pinfunction "GND_61") (pintype "power_in"))
      (node (ref "DD11") (pin "8") (pinfunction "VREFN_8") (pintype "power_in"))
      (node (ref "DD11") (pin "85") (pinfunction "TEST_85") (pintype "input"))
      (node (ref "DD11") (pin "95") (pinfunction "GND_95") (pintype "power_in"))
      (node (ref "DD8") (pin "1") (pinfunction "GND_1") (pintype "input"))
      (node (ref "GQ1") (pin "2") (pinfunction "GND_2") (pintype "power_in"))
      (node (ref "GQ2") (pin "2") (pinfunction "GND_2") (pintype "power_in"))
      (node (ref "J1") (pin "2") (pinfunction "2_2") (pintype "passive"))
      (node (ref "R12") (pin "1") (pinfunction "Pin1_1") (pintype "passive"))
      (node (ref "R7") (pin "1") (pinfunction "Pin1_1") (pintype "passive"))
      (node (ref "XP2") (pin "4") (pinfunction "4_4") (pintype "passive"))
    )
    (net (code "133") (name "Net-(DA2-C)") (class "Default")
      (node (ref "DA2") (pin "1") (pinfunction "C_1") (pintype "input"))
      (node (ref "R5") (pin "2") (pinfunction "Pin2_2") (pintype "passive"))
      (node (ref "VT1") (pin "1") (pinfunction "B_1") (pintype "passive"))
    )
    (net (code "134") (name "Net-(GQ1-OUT)") (class "Default")
      (node (ref "GQ1") (pin "3") (pinfunction "OUT_3") (pintype "output"))
      (node (ref "R1") (pin "1") (pinfunction "Pin1_1") (pintype "passive"))
      (node (ref "R6") (pin "1") (pinfunction "Pin1_1") (pintype "passive"))
    )
    (net (code "135") (name "Net-(GQ2-OUT)") (class "Default")
      (node (ref "GQ2") (pin "3") (pinfunction "OUT_3") (pintype "output"))
      (node (ref "R13") (pin "1") (pinfunction "Pin1_1") (pintype "passive"))
    )
    (net (code "136") (name "REF3V3") (class "Default")
      (node (ref "C27") (pin "1") (pintype "passive"))
      (node (ref "DA21") (pin "1") (pintype "passive"))
      (node (ref "DD11") (pin "9") (pinfunction "VREFP_9") (pintype "power_in"))
      (node (ref "R154") (pin "1") (pinfunction "Pin1_1") (pintype "passive"))
    )
    (net (code "137") (name "unconnected-(DD11A-HSDM-Pad136)") (class "Default")
      (node (ref "DD11") (pin "136") (pinfunction "HSDM_136") (pintype "bidirectional"))
    )
    (net (code "138") (name "unconnected-(DD11A-HSDP-Pad137)") (class "Default")
      (node (ref "DD11") (pin "137") (pinfunction "HSDP_137") (pintype "bidirectional"))
    )
    (net (code "139") (name "unconnected-(DD11A-VBG-Pad140)") (class "Default")
      (node (ref "DD11") (pin "140") (pinfunction "VBG_140") (pintype "input"))
    )
    (net (code "140") (name "unconnected-(DD11A-VDDIN-Pad5)") (class "Default")
      (node (ref "DD11") (pin "5") (pinfunction "VDDIN_5") (pintype "power_in"))
    )
    (net (code "141") (name "unconnected-(DD11A-VDDOUT-Pad3)") (class "Default")
      (node (ref "DD11") (pin "3") (pinfunction "VDDOUT_3") (pintype "power_in"))
    )
    (net (code "142") (name "unconnected-(DD11B-PA0{slash}PWMC0_H0{slash}TIOA0{slash}A17{slash}BA1-Pad102)") (class "Default")
      (node (ref "DD11") (pin "102") (pinfunction "PA0/PWMC0_H0/TIOA0/A17/BA1_102") (pintype "bidirectional"))
    )
    (net (code "143") (name "unconnected-(DD11B-PA11{slash}QCS{slash}PWMC0_H0{slash}PWMC1_L0-Pad64)") (class "Default")
      (node (ref "DD11") (pin "64") (pinfunction "PA11/QCS/PWMC0_H0/PWMC1_L0_64") (pintype "bidirectional"))
    )
    (net (code "144") (name "unconnected-(DD11B-PA12{slash}QIO1{slash}PWMC0_H1{slash}PWMC1_H0-Pad68)") (class "Default")
      (node (ref "DD11") (pin "68") (pinfunction "PA12/QIO1/PWMC0_H1/PWMC1_H0_68") (pintype "bidirectional"))
    )
    (net (code "145") (name "unconnected-(DD11B-PA13{slash}QIO0{slash}PWMC0_H2{slash}PWMC1_L1-Pad42)") (class "Default")
      (node (ref "DD11") (pin "42") (pinfunction "PA13/QIO0/PWMC0_H2/PWMC1_L1_42") (pintype "bidirectional"))
    )
    (net (code "146") (name "unconnected-(DD11B-PA14{slash}QSCK{slash}PWMC0_H3{slash}PWMC1_H1-Pad51)") (class "Default")
      (node (ref "DD11") (pin "51") (pinfunction "PA14/QSCK/PWMC0_H3/PWMC1_H1_51") (pintype "bidirectional"))
    )
    (net (code "147") (name "unconnected-(DD11B-PA17{slash}AFE0_AD6{slash}QIO2{slash}PCK1{slash}PWMC0_H3-Pad25)") (class "Default")
      (node (ref "DD11") (pin "25") (pinfunction "PA17/AFE0_AD6/QIO2/PCK1/PWMC0_H3_25") (pintype "bidirectional"))
    )
    (net (code "148") (name "unconnected-(DD11B-PA26{slash}DCD1{slash}TIOA2{slash}MCDA2{slash}PWMC1_FI1-Pad62)") (class "Default")
      (node (ref "DD11") (pin "62") (pinfunction "PA26/DCD1/TIOA2/MCDA2/PWMC1_FI1_62") (pintype "bidirectional"))
    )
    (net (code "149") (name "unconnected-(DD11B-PC26{slash}AFE1_AD7{slash}A8{slash}TIOA4{slash}SPI1_MISO-Pad13)") (class "Default")
      (node (ref "DD11") (pin "13") (pinfunction "PC26/AFE1_AD7/A8/TIOA4/SPI1_MISO_13") (pintype "bidirectional"))
    )
    (net (code "150") (name "unconnected-(DD11B-PC27{slash}AFE1_AD8{slash}A9{slash}TIOB4{slash}SPI1_MOSI-Pad12)") (class "Default")
      (node (ref "DD11") (pin "12") (pinfunction "PC27/AFE1_AD8/A9/TIOB4/SPI1_MOSI_12") (pintype "bidirectional"))
    )
    (net (code "151") (name "unconnected-(DD11B-PD23{slash}PWMC0_H3{slash}SDCK-Pad57)") (class "Default")
      (node (ref "DD11") (pin "57") (pinfunction "PD23/PWMC0_H3/SDCK_57") (pintype "bidirectional"))
    )
    (net (code "152") (name "unconnected-(DD11B-PD24{slash}PWMC0_L0{slash}RF{slash}TCLK11-Pad55)") (class "Default")
      (node (ref "DD11") (pin "55") (pinfunction "PD24/PWMC0_L0/RF/TCLK11_55") (pintype "bidirectional"))
    )
    (net (code "153") (name "unconnected-(DD11B-PD31{slash}QIO3{slash}UTXD3{slash}PCK2-Pad2)") (class "Default")
      (node (ref "DD11") (pin "2") (pinfunction "PD31/QIO3/UTXD3/PCK2_2") (pintype "bidirectional"))
    )
  )
)
